# p0-001.net
KiCad netlist of a schematic drawn in EAGLE
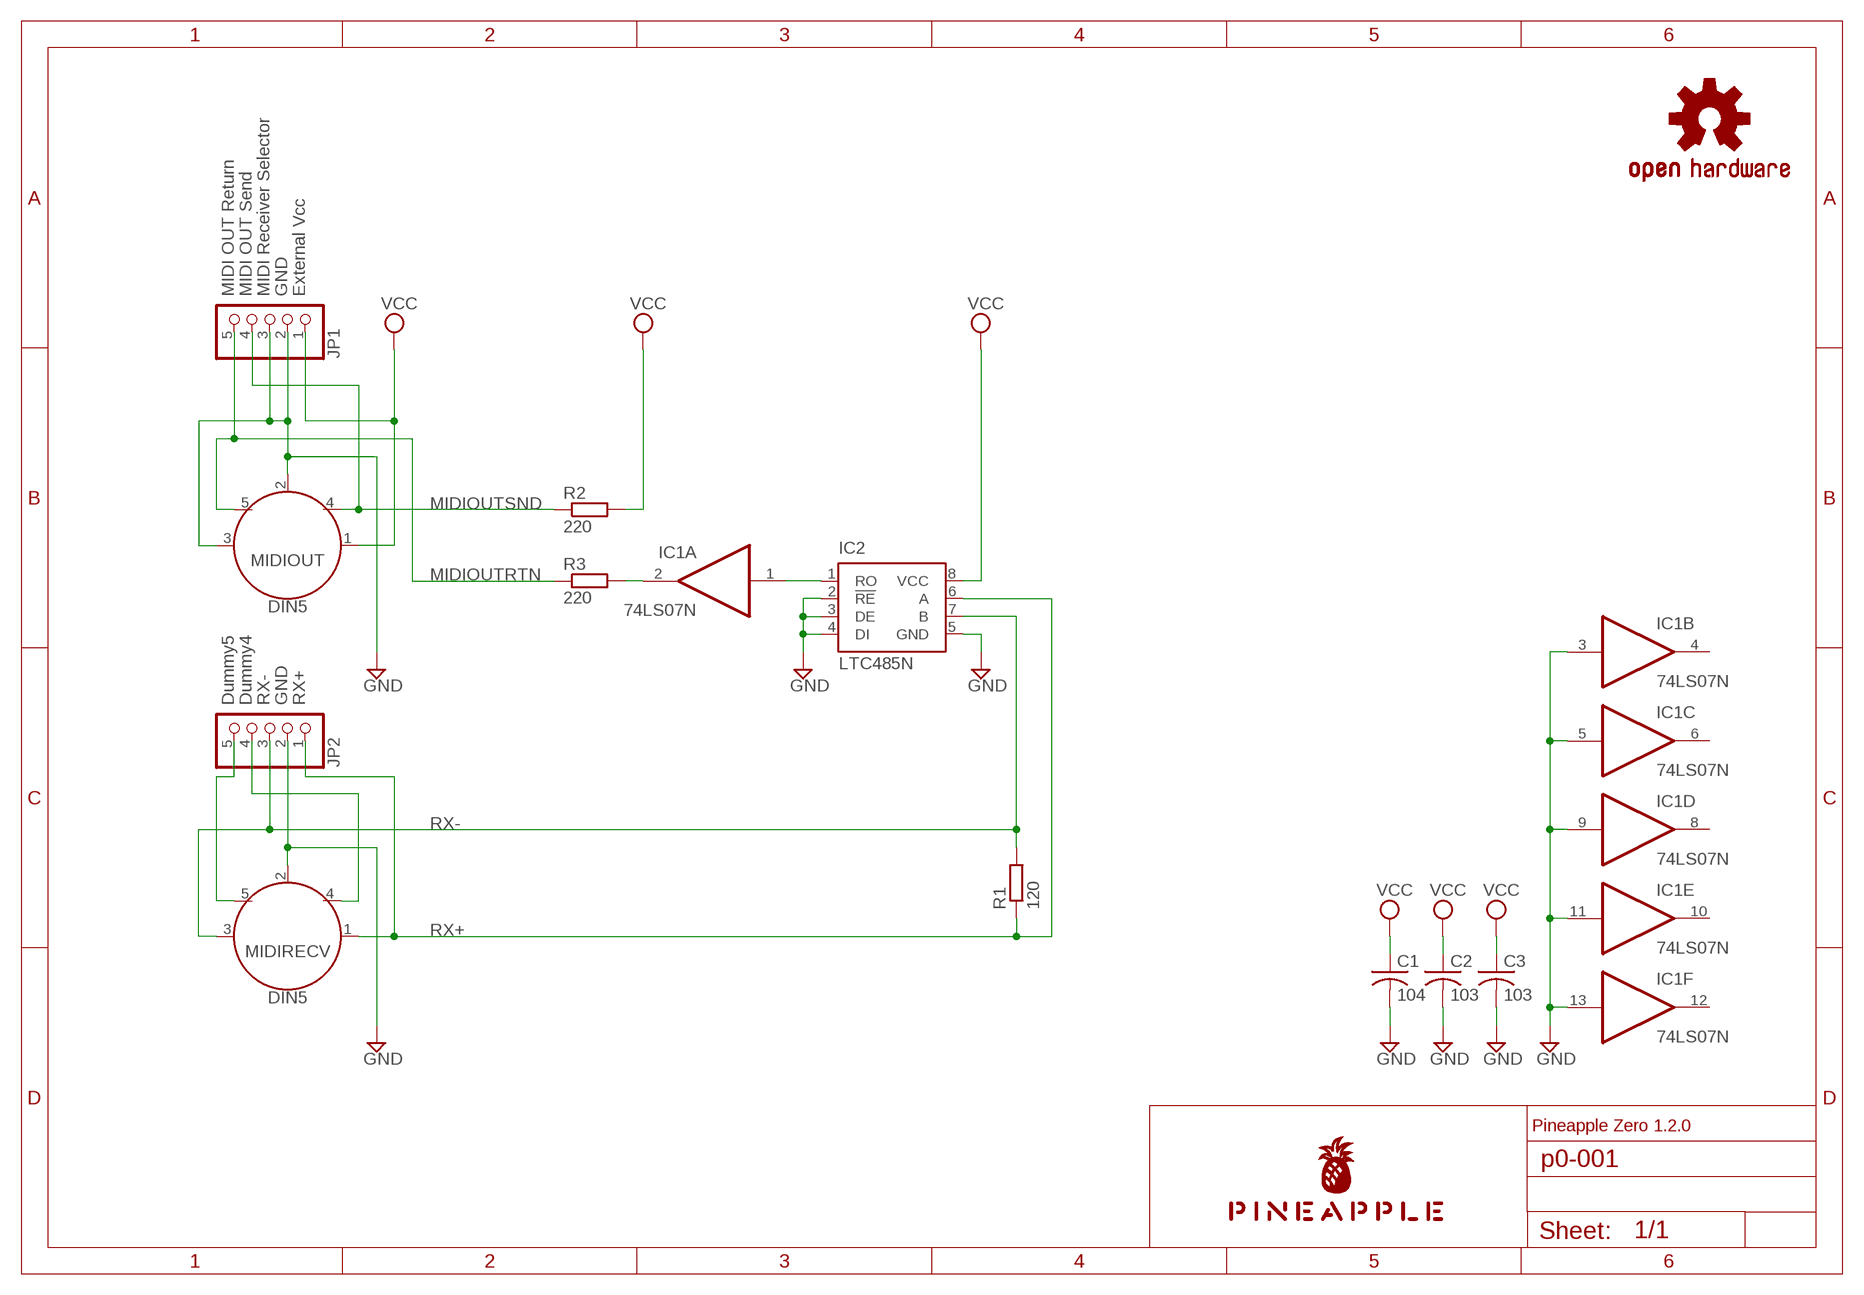
[diagram p0: schematic, sheet 1]

(export (version "E")
  (design (tool "Eeschema 10.0.6"))
  (components
    (comp (ref "C1")
      (value "104")
      (footprint "eagle-import:C025-025X050")
      (libsource (lib "eagle-import") (part "C-US025-025X050"))
    )
    (comp (ref "C2")
      (value "103")
      (footprint "eagle-import:C025-025X050")
      (libsource (lib "eagle-import") (part "C-US025-025X050"))
    )
    (comp (ref "C3")
      (value "103")
      (footprint "eagle-import:C025-025X050")
      (libsource (lib "eagle-import") (part "C-US025-025X050"))
    )
    (comp (ref "IC1")
      (value "74LS07N")
      (footprint "eagle-import:DIL14")
      (libsource (lib "eagle-import") (part "7407NLS"))
    )
    (comp (ref "IC2")
      (value "LTC485N")
      (footprint "eagle-import:DIL08")
      (libsource (lib "eagle-import") (part "LTC485N"))
    )
    (comp (ref "JP1")
      (value "PINHD-1X5")
      (footprint "eagle-import:1X05")
      (libsource (lib "eagle-import") (part "PINHD-1X5"))
    )
    (comp (ref "JP2")
      (value "PINHD-1X5")
      (footprint "eagle-import:1X05")
      (libsource (lib "eagle-import") (part "PINHD-1X5"))
    )
    (comp (ref "LOGO1")
      (value "OSHW-LOGOS-COPPER")
      (footprint "eagle-import:OSHW-LOGO-S_COPPER")
      (libsource (lib "eagle-import") (part "OSHW-LOGOS-COPPER"))
    )
    (comp (ref "MIDIOUT")
      (value "DIN5")
      (footprint "eagle-import:DIN5-RA-PTH")
      (libsource (lib "eagle-import") (part "DIN5"))
    )
    (comp (ref "MIDIRECV")
      (value "DIN5")
      (footprint "eagle-import:DIN5-RA-PTH")
      (libsource (lib "eagle-import") (part "DIN5"))
    )
    (comp (ref "R1")
      (value "120")
      (footprint "eagle-import:0204_5")
      (libsource (lib "eagle-import") (part "R-EU_0204/5"))
    )
    (comp (ref "R2")
      (value "220")
      (footprint "eagle-import:0204_5")
      (libsource (lib "eagle-import") (part "R-EU_0204/5"))
    )
    (comp (ref "R3")
      (value "220")
      (footprint "eagle-import:0204_5")
      (libsource (lib "eagle-import") (part "R-EU_0204/5"))
    )
    (comp (ref "U$1")
      (value "PINEAPPLE450")
      (footprint "eagle-import:PINEAPPLE450")
      (libsource (lib "eagle-import") (part "PINEAPPLE450"))
    )
  )
  (nets
    (net (code "1") (name "/MIDIOUTRTN") (class "Default")
      (node (ref "JP1") (pin "5") (pinfunction "5_5") (pintype "passive"))
      (node (ref "MIDIOUT") (pin "5") (pinfunction "5_5") (pintype "bidirectional"))
      (node (ref "R3") (pin "1") (pinfunction "1_1") (pintype "passive"))
    )
    (net (code "2") (name "/MIDIOUTSND") (class "Default")
      (node (ref "JP1") (pin "4") (pinfunction "4_4") (pintype "passive"))
      (node (ref "MIDIOUT") (pin "4") (pinfunction "4_4") (pintype "bidirectional"))
      (node (ref "R2") (pin "1") (pinfunction "1_1") (pintype "passive"))
    )
    (net (code "3") (name "/RX+") (class "Default")
      (node (ref "IC2") (pin "6") (pinfunction "A_6") (pintype "bidirectional"))
      (node (ref "JP2") (pin "1") (pinfunction "1_1") (pintype "passive"))
      (node (ref "MIDIRECV") (pin "1") (pinfunction "1_1") (pintype "bidirectional"))
      (node (ref "R1") (pin "1") (pinfunction "1_1") (pintype "passive"))
    )
    (net (code "4") (name "/RX-") (class "Default")
      (node (ref "IC2") (pin "7") (pinfunction "B_7") (pintype "bidirectional"))
      (node (ref "JP2") (pin "3") (pinfunction "3_3") (pintype "passive"))
      (node (ref "MIDIRECV") (pin "3") (pinfunction "3_3") (pintype "bidirectional"))
      (node (ref "R1") (pin "2") (pinfunction "2_2") (pintype "passive"))
    )
    (net (code "5") (name "GND") (class "Default")
      (node (ref "C1") (pin "2") (pinfunction "2_2") (pintype "passive"))
      (node (ref "C2") (pin "2") (pinfunction "2_2") (pintype "passive"))
      (node (ref "C3") (pin "2") (pinfunction "2_2") (pintype "passive"))
      (node (ref "IC1") (pin "11") (pinfunction "I_11") (pintype "input"))
      (node (ref "IC1") (pin "13") (pinfunction "I_13") (pintype "input"))
      (node (ref "IC1") (pin "3") (pinfunction "I_3") (pintype "input"))
      (node (ref "IC1") (pin "5") (pinfunction "I_5") (pintype "input"))
      (node (ref "IC1") (pin "9") (pinfunction "I_9") (pintype "input"))
      (node (ref "IC2") (pin "2") (pinfunction "~{RE}_2") (pintype "input"))
      (node (ref "IC2") (pin "3") (pinfunction "DE_3") (pintype "input"))
      (node (ref "IC2") (pin "4") (pinfunction "DI_4") (pintype "input"))
      (node (ref "IC2") (pin "5") (pinfunction "GND_5") (pintype "input"))
      (node (ref "JP1") (pin "2") (pinfunction "2_2") (pintype "passive"))
      (node (ref "JP1") (pin "3") (pinfunction "3_3") (pintype "passive"))
      (node (ref "JP2") (pin "2") (pinfunction "2_2") (pintype "passive"))
      (node (ref "MIDIOUT") (pin "2") (pinfunction "2_2") (pintype "bidirectional"))
      (node (ref "MIDIOUT") (pin "3") (pinfunction "3_3") (pintype "bidirectional"))
      (node (ref "MIDIRECV") (pin "2") (pinfunction "2_2") (pintype "bidirectional"))
    )
    (net (code "6") (name "Net-(IC1A-I)") (class "Default")
      (node (ref "IC1") (pin "1") (pinfunction "I_1") (pintype "input"))
      (node (ref "IC2") (pin "1") (pinfunction "RO_1") (pintype "output"))
    )
    (net (code "7") (name "Net-(IC1A-O)") (class "Default")
      (node (ref "IC1") (pin "2") (pinfunction "O_2") (pintype "open_collector"))
      (node (ref "R3") (pin "2") (pinfunction "2_2") (pintype "passive"))
    )
    (net (code "8") (name "Net-(JP2-Pad4)") (class "Default")
      (node (ref "JP2") (pin "4") (pinfunction "4_4") (pintype "passive"))
      (node (ref "MIDIRECV") (pin "4") (pinfunction "4_4") (pintype "bidirectional"))
    )
    (net (code "9") (name "Net-(JP2-Pad5)") (class "Default")
      (node (ref "JP2") (pin "5") (pinfunction "5_5") (pintype "passive"))
      (node (ref "MIDIRECV") (pin "5") (pinfunction "5_5") (pintype "bidirectional"))
    )
    (net (code "10") (name "VCC") (class "Default")
      (node (ref "C1") (pin "1") (pinfunction "1_1") (pintype "passive"))
      (node (ref "C2") (pin "1") (pinfunction "1_1") (pintype "passive"))
      (node (ref "C3") (pin "1") (pinfunction "1_1") (pintype "passive"))
      (node (ref "IC2") (pin "8") (pinfunction "VCC_8") (pintype "input"))
      (node (ref "JP1") (pin "1") (pinfunction "1_1") (pintype "passive"))
      (node (ref "MIDIOUT") (pin "1") (pinfunction "1_1") (pintype "bidirectional"))
      (node (ref "R2") (pin "2") (pinfunction "2_2") (pintype "passive"))
    )
    (net (code "11") (name "unconnected-(IC1B-O-Pad4)") (class "Default")
      (node (ref "IC1") (pin "4") (pinfunction "O_4") (pintype "open_collector"))
    )
    (net (code "12") (name "unconnected-(IC1C-O-Pad6)") (class "Default")
      (node (ref "IC1") (pin "6") (pinfunction "O_6") (pintype "open_collector"))
    )
    (net (code "13") (name "unconnected-(IC1D-O-Pad8)") (class "Default")
      (node (ref "IC1") (pin "8") (pinfunction "O_8") (pintype "open_collector"))
    )
    (net (code "14") (name "unconnected-(IC1E-O-Pad10)") (class "Default")
      (node (ref "IC1") (pin "10") (pinfunction "O_10") (pintype "open_collector"))
    )
    (net (code "15") (name "unconnected-(IC1F-O-Pad12)") (class "Default")
      (node (ref "IC1") (pin "12") (pinfunction "O_12") (pintype "open_collector"))
    )
  )
)
